# sb-mote2-squat.net
KiCad netlist of a schematic drawn in EAGLE
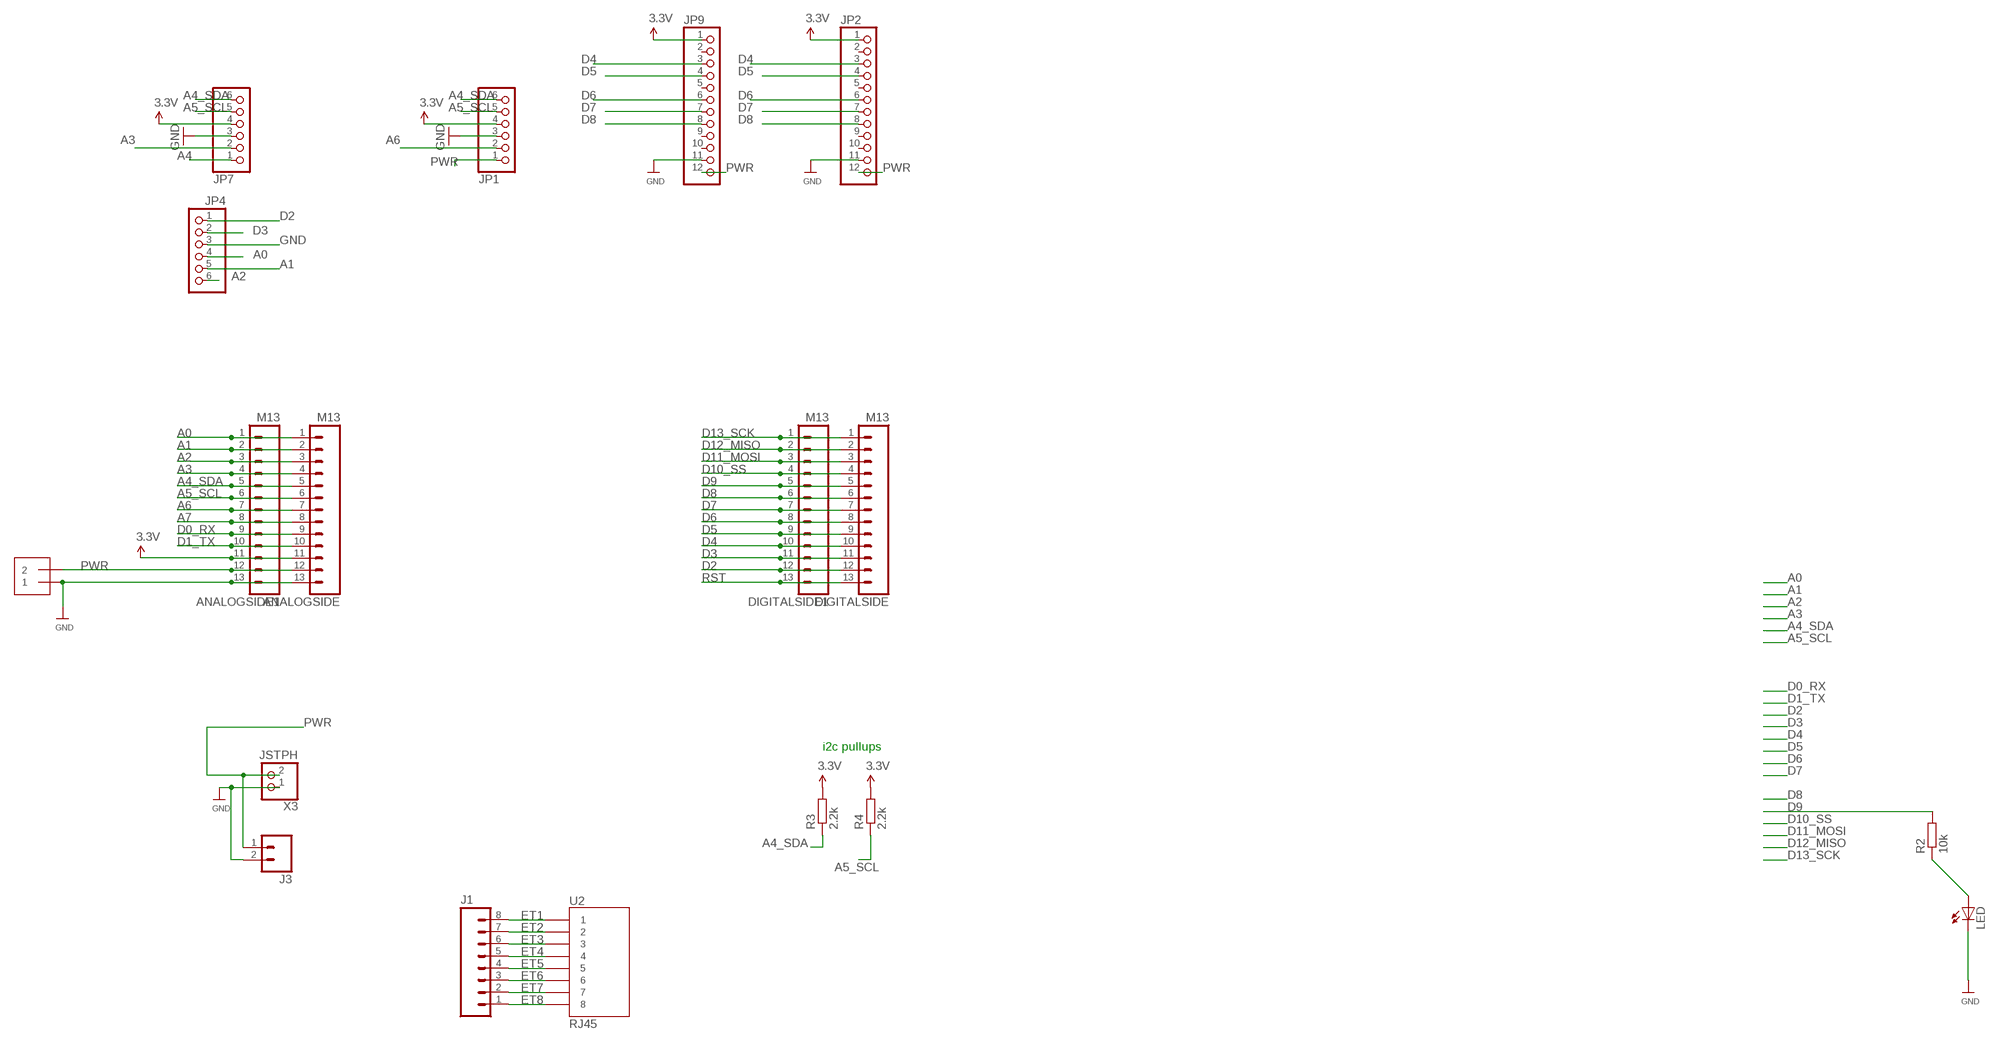
[diagram p0: schematic, sheet 1]

(export (version "E")
  (design (tool "Eeschema 10.0.6"))
  (components
    (comp (ref "ANALOGSIDE")
      (value "M13")
      (footprint "eagle-import:1X13")
      (libsource (lib "eagle-import") (part "M13"))
    )
    (comp (ref "ANALOGSIDE1")
      (value "M13")
      (footprint "eagle-import:1X13")
      (libsource (lib "eagle-import") (part "M13"))
    )
    (comp (ref "DIGITALSIDE")
      (value "M13")
      (footprint "eagle-import:1X13")
      (libsource (lib "eagle-import") (part "M13"))
    )
    (comp (ref "DIGITALSIDE1")
      (value "M13")
      (footprint "eagle-import:1X13")
      (libsource (lib "eagle-import") (part "M13"))
    )
    (comp (ref "J1")
      (value "M08")
      (footprint "eagle-import:1X08_ROUND")
      (libsource (lib "eagle-import") (part "M08"))
    )
    (comp (ref "J2")
      (value "1X2-3.5MM")
      (footprint "eagle-import:1X2-3.5MM")
      (libsource (lib "eagle-import") (part "1X2-3.5MM"))
    )
    (comp (ref "J3")
      (value "M02PTH")
      (footprint "eagle-import:1X02")
      (libsource (lib "eagle-import") (part "M02PTH"))
    )
    (comp (ref "JP1")
      (value "PINHD-1X6-3.5MM")
      (footprint "eagle-import:1X06-3.5MM")
      (libsource (lib "eagle-import") (part "PINHD-1X6-3.5MM"))
    )
    (comp (ref "JP2")
      (value "PINHD-1X12-CB")
      (footprint "eagle-import:1X12-CB")
      (libsource (lib "eagle-import") (part "PINHD-1X12-CB"))
    )
    (comp (ref "JP4")
      (value "PINHD-1X6-3.5MM")
      (footprint "eagle-import:1X06-3.5MM")
      (libsource (lib "eagle-import") (part "PINHD-1X6-3.5MM"))
    )
    (comp (ref "JP7")
      (value "PINHD-1X6-3.5MM")
      (footprint "eagle-import:1X06-3.5MM")
      (libsource (lib "eagle-import") (part "PINHD-1X6-3.5MM"))
    )
    (comp (ref "JP9")
      (value "PINHD-1X12-CB")
      (footprint "eagle-import:1X12-CB")
      (libsource (lib "eagle-import") (part "PINHD-1X12-CB"))
    )
    (comp (ref "LED")
      (value "LED3MM")
      (footprint "eagle-import:LED3MM")
      (libsource (lib "eagle-import") (part "LED3MM"))
    )
    (comp (ref "R2")
      (value "10k")
      (footprint "eagle-import:0204_7")
      (libsource (lib "eagle-import") (part "R-EU_0204/7"))
    )
    (comp (ref "R3")
      (value "2.2k")
      (footprint "eagle-import:0204_7")
      (libsource (lib "eagle-import") (part "R-EU_0204/7"))
    )
    (comp (ref "R4")
      (value "2.2k")
      (footprint "eagle-import:0204_7")
      (libsource (lib "eagle-import") (part "R-EU_0204/7"))
    )
    (comp (ref "U2")
      (value "RJ45")
      (footprint "eagle-import:RJ45-8")
      (libsource (lib "eagle-import") (part "RJ45-8PTH"))
    )
    (comp (ref "X3")
      (value "JSTPH")
      (footprint "eagle-import:JSTPH2")
      (libsource (lib "eagle-import") (part "CON_JST_PH_2PIN"))
    )
  )
  (nets
    (net (code "1") (name "/A0") (class "Default")
      (node (ref "ANALOGSIDE") (pin "1") (pinfunction "1_1") (pintype "passive"))
      (node (ref "ANALOGSIDE1") (pin "1") (pinfunction "1_1") (pintype "passive"))
      (node (ref "JP4") (pin "4") (pinfunction "4_4") (pintype "passive"))
    )
    (net (code "2") (name "/A1") (class "Default")
      (node (ref "ANALOGSIDE") (pin "2") (pinfunction "2_2") (pintype "passive"))
      (node (ref "ANALOGSIDE1") (pin "2") (pinfunction "2_2") (pintype "passive"))
      (node (ref "JP4") (pin "5") (pinfunction "5_5") (pintype "passive"))
    )
    (net (code "3") (name "/A2") (class "Default")
      (node (ref "ANALOGSIDE") (pin "3") (pinfunction "3_3") (pintype "passive"))
      (node (ref "ANALOGSIDE1") (pin "3") (pinfunction "3_3") (pintype "passive"))
      (node (ref "JP4") (pin "6") (pinfunction "6_6") (pintype "passive"))
    )
    (net (code "4") (name "/A3") (class "Default")
      (node (ref "ANALOGSIDE") (pin "4") (pinfunction "4_4") (pintype "passive"))
      (node (ref "ANALOGSIDE1") (pin "4") (pinfunction "4_4") (pintype "passive"))
      (node (ref "JP7") (pin "2") (pinfunction "2_2") (pintype "passive"))
    )
    (net (code "5") (name "/A4") (class "Default")
      (node (ref "JP7") (pin "1") (pinfunction "1_1") (pintype "passive"))
    )
    (net (code "6") (name "/A4_SDA") (class "Default")
      (node (ref "ANALOGSIDE") (pin "5") (pinfunction "5_5") (pintype "passive"))
      (node (ref "ANALOGSIDE1") (pin "5") (pinfunction "5_5") (pintype "passive"))
      (node (ref "JP1") (pin "6") (pinfunction "6_6") (pintype "passive"))
      (node (ref "JP7") (pin "6") (pinfunction "6_6") (pintype "passive"))
      (node (ref "R3") (pin "1") (pinfunction "1_1") (pintype "passive"))
    )
    (net (code "7") (name "/A5_SCL") (class "Default")
      (node (ref "ANALOGSIDE") (pin "6") (pinfunction "6_6") (pintype "passive"))
      (node (ref "ANALOGSIDE1") (pin "6") (pinfunction "6_6") (pintype "passive"))
      (node (ref "JP1") (pin "5") (pinfunction "5_5") (pintype "passive"))
      (node (ref "JP7") (pin "5") (pinfunction "5_5") (pintype "passive"))
      (node (ref "R4") (pin "1") (pinfunction "1_1") (pintype "passive"))
    )
    (net (code "8") (name "/A6") (class "Default")
      (node (ref "ANALOGSIDE") (pin "7") (pinfunction "7_7") (pintype "passive"))
      (node (ref "ANALOGSIDE1") (pin "7") (pinfunction "7_7") (pintype "passive"))
      (node (ref "JP1") (pin "2") (pinfunction "2_2") (pintype "passive"))
    )
    (net (code "9") (name "/A7") (class "Default")
      (node (ref "ANALOGSIDE") (pin "8") (pinfunction "8_8") (pintype "passive"))
      (node (ref "ANALOGSIDE1") (pin "8") (pinfunction "8_8") (pintype "passive"))
    )
    (net (code "10") (name "/D0_RX") (class "Default")
      (node (ref "ANALOGSIDE") (pin "9") (pinfunction "9_9") (pintype "passive"))
      (node (ref "ANALOGSIDE1") (pin "9") (pinfunction "9_9") (pintype "passive"))
    )
    (net (code "11") (name "/D1_TX") (class "Default")
      (node (ref "ANALOGSIDE") (pin "10") (pinfunction "10_10") (pintype "passive"))
      (node (ref "ANALOGSIDE1") (pin "10") (pinfunction "10_10") (pintype "passive"))
    )
    (net (code "12") (name "/D2") (class "Default")
      (node (ref "DIGITALSIDE") (pin "12") (pinfunction "12_12") (pintype "passive"))
      (node (ref "DIGITALSIDE1") (pin "12") (pinfunction "12_12") (pintype "passive"))
      (node (ref "JP4") (pin "1") (pinfunction "1_1") (pintype "passive"))
    )
    (net (code "13") (name "/D3") (class "Default")
      (node (ref "DIGITALSIDE") (pin "11") (pinfunction "11_11") (pintype "passive"))
      (node (ref "DIGITALSIDE1") (pin "11") (pinfunction "11_11") (pintype "passive"))
      (node (ref "JP4") (pin "2") (pinfunction "2_2") (pintype "passive"))
    )
    (net (code "14") (name "/D4") (class "Default")
      (node (ref "DIGITALSIDE") (pin "10") (pinfunction "10_10") (pintype "passive"))
      (node (ref "DIGITALSIDE1") (pin "10") (pinfunction "10_10") (pintype "passive"))
      (node (ref "JP2") (pin "3") (pinfunction "3_3") (pintype "passive"))
      (node (ref "JP9") (pin "3") (pinfunction "3_3") (pintype "passive"))
    )
    (net (code "15") (name "/D5") (class "Default")
      (node (ref "DIGITALSIDE") (pin "9") (pinfunction "9_9") (pintype "passive"))
      (node (ref "DIGITALSIDE1") (pin "9") (pinfunction "9_9") (pintype "passive"))
      (node (ref "JP2") (pin "4") (pinfunction "4_4") (pintype "passive"))
      (node (ref "JP9") (pin "4") (pinfunction "4_4") (pintype "passive"))
    )
    (net (code "16") (name "/D6") (class "Default")
      (node (ref "DIGITALSIDE") (pin "8") (pinfunction "8_8") (pintype "passive"))
      (node (ref "DIGITALSIDE1") (pin "8") (pinfunction "8_8") (pintype "passive"))
      (node (ref "JP2") (pin "6") (pinfunction "6_6") (pintype "passive"))
      (node (ref "JP9") (pin "6") (pinfunction "6_6") (pintype "passive"))
    )
    (net (code "17") (name "/D7") (class "Default")
      (node (ref "DIGITALSIDE") (pin "7") (pinfunction "7_7") (pintype "passive"))
      (node (ref "DIGITALSIDE1") (pin "7") (pinfunction "7_7") (pintype "passive"))
      (node (ref "JP2") (pin "7") (pinfunction "7_7") (pintype "passive"))
      (node (ref "JP9") (pin "7") (pinfunction "7_7") (pintype "passive"))
    )
    (net (code "18") (name "/D8") (class "Default")
      (node (ref "DIGITALSIDE") (pin "6") (pinfunction "6_6") (pintype "passive"))
      (node (ref "DIGITALSIDE1") (pin "6") (pinfunction "6_6") (pintype "passive"))
      (node (ref "JP2") (pin "8") (pinfunction "8_8") (pintype "passive"))
      (node (ref "JP9") (pin "8") (pinfunction "8_8") (pintype "passive"))
    )
    (net (code "19") (name "/D9") (class "Default")
      (node (ref "DIGITALSIDE") (pin "5") (pinfunction "5_5") (pintype "passive"))
      (node (ref "DIGITALSIDE1") (pin "5") (pinfunction "5_5") (pintype "passive"))
      (node (ref "R2") (pin "2") (pinfunction "2_2") (pintype "passive"))
    )
    (net (code "20") (name "/D10_SS") (class "Default")
      (node (ref "DIGITALSIDE") (pin "4") (pinfunction "4_4") (pintype "passive"))
      (node (ref "DIGITALSIDE1") (pin "4") (pinfunction "4_4") (pintype "passive"))
    )
    (net (code "21") (name "/D11_MOSI") (class "Default")
      (node (ref "DIGITALSIDE") (pin "3") (pinfunction "3_3") (pintype "passive"))
      (node (ref "DIGITALSIDE1") (pin "3") (pinfunction "3_3") (pintype "passive"))
    )
    (net (code "22") (name "/D12_MISO") (class "Default")
      (node (ref "DIGITALSIDE") (pin "2") (pinfunction "2_2") (pintype "passive"))
      (node (ref "DIGITALSIDE1") (pin "2") (pinfunction "2_2") (pintype "passive"))
    )
    (net (code "23") (name "/D13_SCK") (class "Default")
      (node (ref "DIGITALSIDE") (pin "1") (pinfunction "1_1") (pintype "passive"))
      (node (ref "DIGITALSIDE1") (pin "1") (pinfunction "1_1") (pintype "passive"))
    )
    (net (code "24") (name "/ET1") (class "Default")
      (node (ref "J1") (pin "8") (pinfunction "8_8") (pintype "passive"))
      (node (ref "U2") (pin "1") (pinfunction "1_1") (pintype "bidirectional"))
    )
    (net (code "25") (name "/ET2") (class "Default")
      (node (ref "J1") (pin "7") (pinfunction "7_7") (pintype "passive"))
      (node (ref "U2") (pin "2") (pinfunction "2_2") (pintype "bidirectional"))
    )
    (net (code "26") (name "/ET3") (class "Default")
      (node (ref "J1") (pin "6") (pinfunction "6_6") (pintype "passive"))
      (node (ref "U2") (pin "3") (pinfunction "3_3") (pintype "bidirectional"))
    )
    (net (code "27") (name "/ET4") (class "Default")
      (node (ref "J1") (pin "5") (pinfunction "5_5") (pintype "passive"))
      (node (ref "U2") (pin "4") (pinfunction "4_4") (pintype "bidirectional"))
    )
    (net (code "28") (name "/ET5") (class "Default")
      (node (ref "J1") (pin "4") (pinfunction "4_4") (pintype "passive"))
      (node (ref "U2") (pin "5") (pinfunction "5_5") (pintype "bidirectional"))
    )
    (net (code "29") (name "/ET6") (class "Default")
      (node (ref "J1") (pin "3") (pinfunction "3_3") (pintype "passive"))
      (node (ref "U2") (pin "6") (pinfunction "6_6") (pintype "bidirectional"))
    )
    (net (code "30") (name "/ET7") (class "Default")
      (node (ref "J1") (pin "2") (pinfunction "2_2") (pintype "passive"))
      (node (ref "U2") (pin "7") (pinfunction "7_7") (pintype "bidirectional"))
    )
    (net (code "31") (name "/ET8") (class "Default")
      (node (ref "J1") (pin "1") (pinfunction "1_1") (pintype "passive"))
      (node (ref "U2") (pin "8") (pinfunction "8_8") (pintype "bidirectional"))
    )
    (net (code "32") (name "/PWR") (class "Default")
      (node (ref "ANALOGSIDE") (pin "12") (pinfunction "12_12") (pintype "passive"))
      (node (ref "ANALOGSIDE1") (pin "12") (pinfunction "12_12") (pintype "passive"))
      (node (ref "J2") (pin "2") (pinfunction "2_2") (pintype "passive"))
      (node (ref "J3") (pin "1") (pinfunction "1_1") (pintype "passive"))
      (node (ref "JP1") (pin "1") (pinfunction "1_1") (pintype "passive"))
      (node (ref "JP2") (pin "12") (pinfunction "12_12") (pintype "passive"))
      (node (ref "JP9") (pin "12") (pinfunction "12_12") (pintype "passive"))
      (node (ref "X3") (pin "2") (pinfunction "2_2") (pintype "passive"))
    )
    (net (code "33") (name "/RST") (class "Default")
      (node (ref "DIGITALSIDE") (pin "13") (pinfunction "13_13") (pintype "passive"))
      (node (ref "DIGITALSIDE1") (pin "13") (pinfunction "13_13") (pintype "passive"))
    )
    (net (code "34") (name "3.3V") (class "Default")
      (node (ref "ANALOGSIDE") (pin "11") (pinfunction "11_11") (pintype "passive"))
      (node (ref "ANALOGSIDE1") (pin "11") (pinfunction "11_11") (pintype "passive"))
      (node (ref "JP1") (pin "4") (pinfunction "4_4") (pintype "passive"))
      (node (ref "JP2") (pin "1") (pinfunction "1_1") (pintype "passive"))
      (node (ref "JP7") (pin "4") (pinfunction "4_4") (pintype "passive"))
      (node (ref "JP9") (pin "1") (pinfunction "1_1") (pintype "passive"))
      (node (ref "R3") (pin "2") (pinfunction "2_2") (pintype "passive"))
      (node (ref "R4") (pin "2") (pinfunction "2_2") (pintype "passive"))
    )
    (net (code "35") (name "GND") (class "Default")
      (node (ref "ANALOGSIDE") (pin "13") (pinfunction "13_13") (pintype "passive"))
      (node (ref "ANALOGSIDE1") (pin "13") (pinfunction "13_13") (pintype "passive"))
      (node (ref "J2") (pin "1") (pinfunction "1_1") (pintype "passive"))
      (node (ref "J3") (pin "2") (pinfunction "2_2") (pintype "passive"))
      (node (ref "JP1") (pin "3") (pinfunction "3_3") (pintype "passive"))
      (node (ref "JP2") (pin "11") (pinfunction "11_11") (pintype "passive"))
      (node (ref "JP4") (pin "3") (pinfunction "3_3") (pintype "passive"))
      (node (ref "JP7") (pin "3") (pinfunction "3_3") (pintype "passive"))
      (node (ref "JP9") (pin "11") (pinfunction "11_11") (pintype "passive"))
      (node (ref "LED") (pin "K") (pinfunction "C_K") (pintype "passive"))
      (node (ref "X3") (pin "1") (pinfunction "1_1") (pintype "passive"))
    )
    (net (code "36") (name "Net-(LED-PadA)") (class "Default")
      (node (ref "LED") (pin "A") (pinfunction "A_A") (pintype "passive"))
      (node (ref "R2") (pin "1") (pinfunction "1_1") (pintype "passive"))
    )
    (net (code "37") (name "unconnected-(JP2-Pad2)") (class "Default")
      (node (ref "JP2") (pin "2") (pinfunction "2_2") (pintype "passive"))
    )
    (net (code "38") (name "unconnected-(JP2-Pad5)") (class "Default")
      (node (ref "JP2") (pin "5") (pinfunction "5_5") (pintype "passive"))
    )
    (net (code "39") (name "unconnected-(JP2-Pad9)") (class "Default")
      (node (ref "JP2") (pin "9") (pinfunction "9_9") (pintype "passive"))
    )
    (net (code "40") (name "unconnected-(JP2-Pad10)") (class "Default")
      (node (ref "JP2") (pin "10") (pinfunction "10_10") (pintype "passive"))
    )
    (net (code "41") (name "unconnected-(JP9-Pad2)") (class "Default")
      (node (ref "JP9") (pin "2") (pinfunction "2_2") (pintype "passive"))
    )
    (net (code "42") (name "unconnected-(JP9-Pad5)") (class "Default")
      (node (ref "JP9") (pin "5") (pinfunction "5_5") (pintype "passive"))
    )
    (net (code "43") (name "unconnected-(JP9-Pad9)") (class "Default")
      (node (ref "JP9") (pin "9") (pinfunction "9_9") (pintype "passive"))
    )
    (net (code "44") (name "unconnected-(JP9-Pad10)") (class "Default")
      (node (ref "JP9") (pin "10") (pinfunction "10_10") (pintype "passive"))
    )
  )
)
